# MCP73213.net
KiCad netlist of a schematic drawn in EAGLE
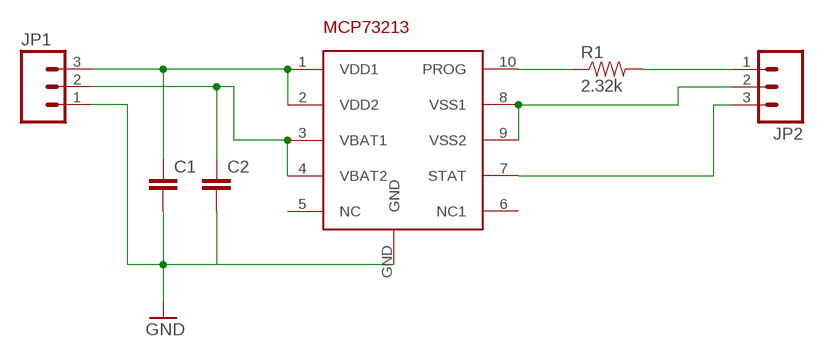
[diagram p0: schematic, sheet 1]

(export (version "E")
  (design (tool "Eeschema 10.0.6"))
  (components
    (comp (ref "C1")
      (value "CAP0805")
      (footprint "eagle-import:0805")
      (libsource (lib "eagle-import") (part "CAP0805"))
    )
    (comp (ref "C2")
      (value "CAP0805")
      (footprint "eagle-import:0805")
      (libsource (lib "eagle-import") (part "CAP0805"))
    )
    (comp (ref "JP1")
      (value "M03LOCK")
      (footprint "eagle-import:1X03_LOCK")
      (libsource (lib "eagle-import") (part "M03LOCK"))
    )
    (comp (ref "JP2")
      (value "M03LOCK")
      (footprint "eagle-import:1X03_LOCK")
      (libsource (lib "eagle-import") (part "M03LOCK"))
    )
    (comp (ref "R1")
      (value "2.32k")
      (footprint "eagle-import:0805")
      (libsource (lib "eagle-import") (part "RESISTOR0805-RES"))
    )
    (comp (ref "U$1")
      (value "MCP73213")
      (footprint "eagle-import:DFN10_3X3MM")
      (libsource (lib "eagle-import") (part "MCP73213"))
    )
  )
  (nets
    (net (code "1") (name "GND") (class "Default")
      (node (ref "C1") (pin "2") (pinfunction "2_2") (pintype "passive"))
      (node (ref "C2") (pin "2") (pinfunction "2_2") (pintype "passive"))
      (node (ref "JP1") (pin "1") (pinfunction "1_1") (pintype "passive"))
      (node (ref "U$1") (pin "GND") (pinfunction "GND_GND") (pintype "bidirectional"))
    )
    (net (code "2") (name "Net-(JP2-Pad1)") (class "Default")
      (node (ref "JP2") (pin "1") (pinfunction "1_1") (pintype "passive"))
      (node (ref "R1") (pin "2") (pinfunction "2_2") (pintype "passive"))
    )
    (net (code "3") (name "Net-(U$1-PROG)") (class "Default")
      (node (ref "R1") (pin "1") (pinfunction "1_1") (pintype "passive"))
      (node (ref "U$1") (pin "10") (pinfunction "PROG_10") (pintype "bidirectional"))
    )
    (net (code "4") (name "Net-(U$1-STAT)") (class "Default")
      (node (ref "JP2") (pin "3") (pinfunction "3_3") (pintype "passive"))
      (node (ref "U$1") (pin "7") (pinfunction "STAT_7") (pintype "bidirectional"))
    )
    (net (code "5") (name "Net-(U$1-VBAT1)") (class "Default")
      (node (ref "C2") (pin "1") (pinfunction "1_1") (pintype "passive"))
      (node (ref "JP1") (pin "2") (pinfunction "2_2") (pintype "passive"))
      (node (ref "U$1") (pin "3") (pinfunction "VBAT1_3") (pintype "bidirectional"))
      (node (ref "U$1") (pin "4") (pinfunction "VBAT2_4") (pintype "bidirectional"))
    )
    (net (code "6") (name "Net-(U$1-VDD1)") (class "Default")
      (node (ref "C1") (pin "1") (pinfunction "1_1") (pintype "passive"))
      (node (ref "JP1") (pin "3") (pinfunction "3_3") (pintype "passive"))
      (node (ref "U$1") (pin "1") (pinfunction "VDD1_1") (pintype "bidirectional"))
      (node (ref "U$1") (pin "2") (pinfunction "VDD2_2") (pintype "bidirectional"))
    )
    (net (code "7") (name "Net-(U$1-VSS1)") (class "Default")
      (node (ref "JP2") (pin "2") (pinfunction "2_2") (pintype "passive"))
      (node (ref "U$1") (pin "8") (pinfunction "VSS1_8") (pintype "bidirectional"))
      (node (ref "U$1") (pin "9") (pinfunction "VSS2_9") (pintype "bidirectional"))
    )
    (net (code "8") (name "unconnected-(U$1-NC-Pad5)") (class "Default")
      (node (ref "U$1") (pin "5") (pinfunction "NC_5") (pintype "bidirectional"))
    )
    (net (code "9") (name "unconnected-(U$1-NC1-Pad6)") (class "Default")
      (node (ref "U$1") (pin "6") (pinfunction "NC1_6") (pintype "bidirectional"))
    )
  )
)
